# schema.net
KiCad netlist of a schematic drawn in EAGLE
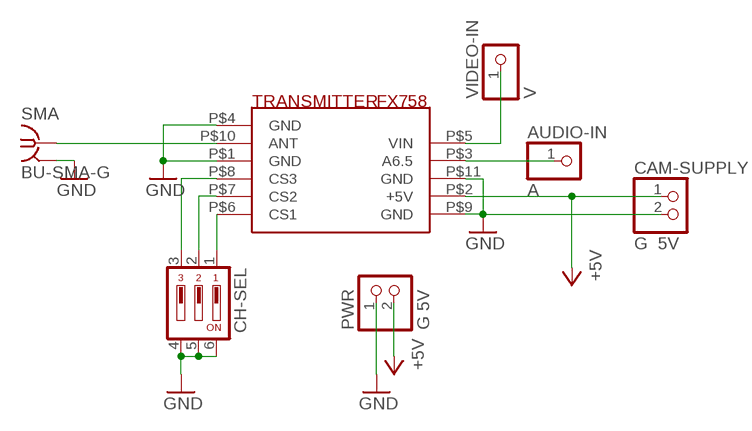
[diagram p0: schematic, sheet 1]

(export (version "E")
  (design (tool "Eeschema 10.0.6"))
  (components
    (comp (ref "AUDIO-IN")
      (value "A")
      (footprint "eagle-import:1X01")
      (libsource (lib "eagle-import") (part "PINHD-1X1"))
    )
    (comp (ref "CAM-SUPPLY")
      (value "G 5V")
      (footprint "eagle-import:1X02")
      (libsource (lib "eagle-import") (part "PINHD-1X2"))
    )
    (comp (ref "CH-SEL")
      (value "DP03")
      (footprint "eagle-import:DP-03")
      (fields (field (name "MPN") "MCDP03"))
      (libsource (lib "eagle-import") (part "DP03"))
    )
    (comp (ref "PWR")
      (value "G 5V")
      (footprint "eagle-import:1X02")
      (libsource (lib "eagle-import") (part "PINHD-1X2"))
    )
    (comp (ref "SMA")
      (value "BU-SMA-G")
      (footprint "eagle-import:BU-SMA-G")
      (libsource (lib "eagle-import") (part "BU-SMA-G"))
    )
    (comp (ref "TRANSMITTER")
      (value "FX758")
      (footprint "eagle-import:FX758")
      (libsource (lib "eagle-import") (part "FX758"))
    )
    (comp (ref "VIDEO-IN")
      (value "V")
      (footprint "eagle-import:1X01")
      (libsource (lib "eagle-import") (part "PINHD-1X1"))
    )
  )
  (nets
    (net (code "1") (name "+5V") (class "Default")
      (node (ref "CAM-SUPPLY") (pin "1") (pinfunction "1_1") (pintype "passive"))
      (node (ref "PWR") (pin "2") (pinfunction "2_2") (pintype "passive"))
      (node (ref "TRANSMITTER") (pin "P$2") (pinfunction "+5V_P$2") (pintype "bidirectional"))
    )
    (net (code "2") (name "GND") (class "Default")
      (node (ref "CAM-SUPPLY") (pin "2") (pinfunction "2_2") (pintype "passive"))
      (node (ref "CH-SEL") (pin "4") (pinfunction "4_4") (pintype "passive"))
      (node (ref "CH-SEL") (pin "5") (pinfunction "5_5") (pintype "passive"))
      (node (ref "CH-SEL") (pin "6") (pinfunction "6_6") (pintype "passive"))
      (node (ref "PWR") (pin "1") (pinfunction "1_1") (pintype "passive"))
      (node (ref "SMA") (pin "2") (pinfunction "2_2") (pintype "passive"))
      (node (ref "SMA") (pin "3") (pinfunction "2_3") (pintype "passive"))
      (node (ref "SMA") (pin "4") (pinfunction "2_4") (pintype "passive"))
      (node (ref "SMA") (pin "5") (pinfunction "2_5") (pintype "passive"))
      (node (ref "TRANSMITTER") (pin "P$1") (pinfunction "GND_P$1") (pintype "bidirectional"))
      (node (ref "TRANSMITTER") (pin "P$11") (pinfunction "GND_P$11") (pintype "bidirectional"))
      (node (ref "TRANSMITTER") (pin "P$4") (pinfunction "GND_P$4") (pintype "bidirectional"))
      (node (ref "TRANSMITTER") (pin "P$9") (pinfunction "GND_P$9") (pintype "bidirectional"))
    )
    (net (code "3") (name "Net-(TRANSMITTER-A6.5)") (class "Default")
      (node (ref "AUDIO-IN") (pin "1") (pinfunction "1_1") (pintype "passive"))
      (node (ref "TRANSMITTER") (pin "P$3") (pinfunction "A6.5_P$3") (pintype "bidirectional"))
    )
    (net (code "4") (name "Net-(TRANSMITTER-ANT)") (class "Default")
      (node (ref "SMA") (pin "1") (pinfunction "1_1") (pintype "passive"))
      (node (ref "TRANSMITTER") (pin "P$10") (pinfunction "ANT_P$10") (pintype "bidirectional"))
    )
    (net (code "5") (name "Net-(TRANSMITTER-CS1)") (class "Default")
      (node (ref "CH-SEL") (pin "1") (pinfunction "1_1") (pintype "passive"))
      (node (ref "TRANSMITTER") (pin "P$6") (pinfunction "CS1_P$6") (pintype "bidirectional"))
    )
    (net (code "6") (name "Net-(TRANSMITTER-CS2)") (class "Default")
      (node (ref "CH-SEL") (pin "2") (pinfunction "2_2") (pintype "passive"))
      (node (ref "TRANSMITTER") (pin "P$7") (pinfunction "CS2_P$7") (pintype "bidirectional"))
    )
    (net (code "7") (name "Net-(TRANSMITTER-CS3)") (class "Default")
      (node (ref "CH-SEL") (pin "3") (pinfunction "3_3") (pintype "passive"))
      (node (ref "TRANSMITTER") (pin "P$8") (pinfunction "CS3_P$8") (pintype "bidirectional"))
    )
    (net (code "8") (name "Net-(TRANSMITTER-VIN)") (class "Default")
      (node (ref "TRANSMITTER") (pin "P$5") (pinfunction "VIN_P$5") (pintype "bidirectional"))
      (node (ref "VIDEO-IN") (pin "1") (pinfunction "1_1") (pintype "passive"))
    )
  )
)
